# Sheet1.net
KiCad netlist of a schematic drawn in Altium Designer
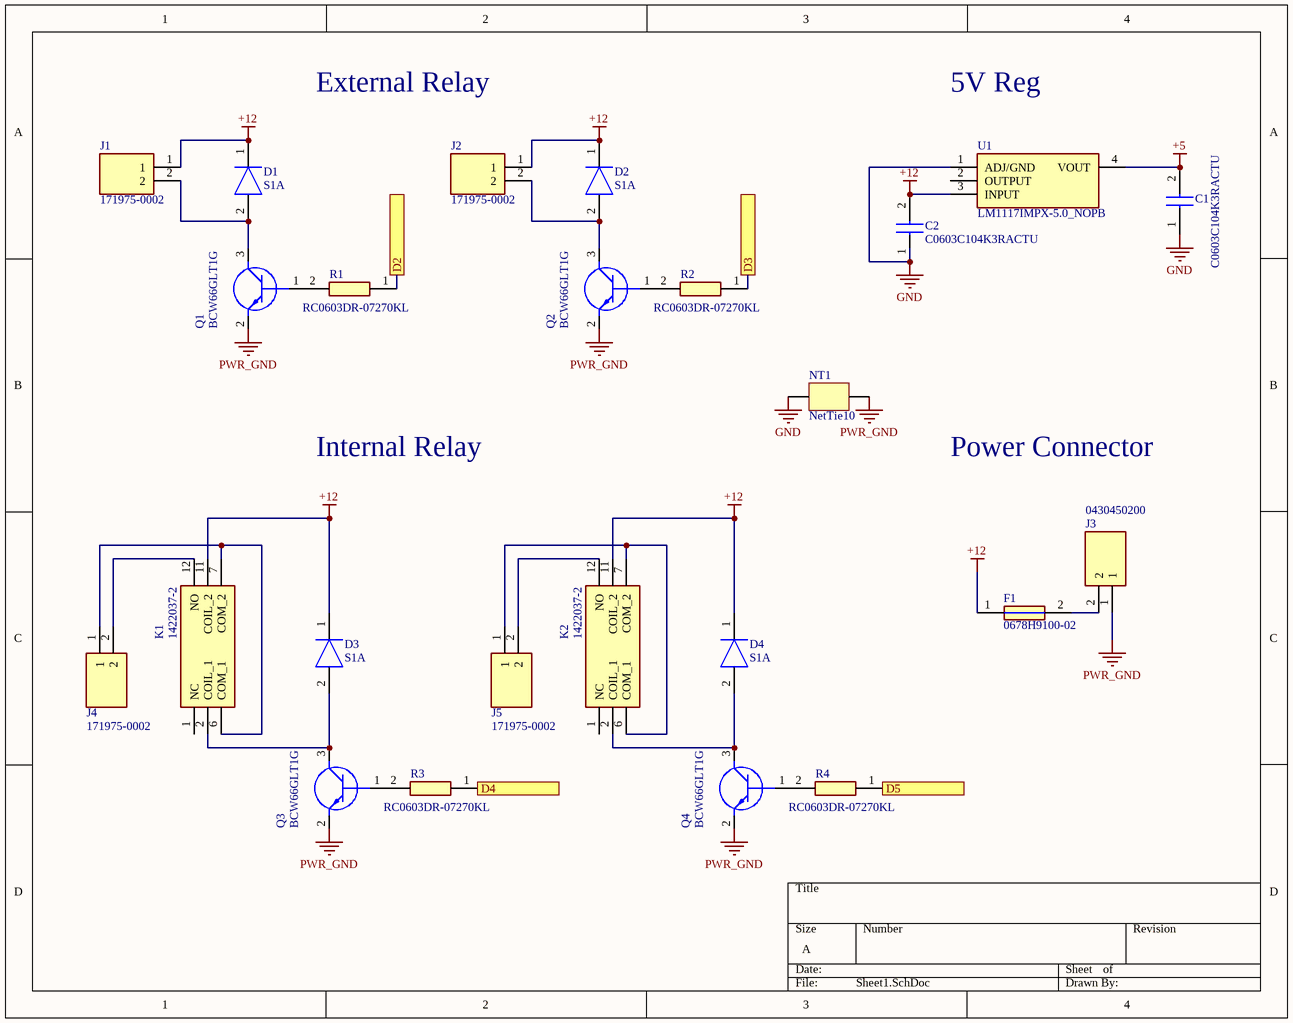
[diagram p0: Sheet1.SchDoc]

(export (version "E")
  (design (tool "Eeschema 10.0.6"))
  (components
    (comp (ref "C1")
      (value "C0603C104K3RACTU")
      (footprint "SamacSys:CAPC1608X95N")
      (description "Capacitor")
      (fields (field (name "MOUSER PART NUMBER") "80-C0603C104K3R"))
      (libsource (lib "*") (part "C0603C104K3RACTU"))
    )
    (comp (ref "C2")
      (value "C0603C104K3RACTU")
      (footprint "SamacSys:CAPC1608X95N")
      (description "Capacitor")
      (fields (field (name "MOUSER PART NUMBER") "80-C0603C104K3R"))
      (libsource (lib "*") (part "C0603C104K3RACTU"))
    )
    (comp (ref "D1")
      (value "S1A")
      (footprint "SamacSys:DIOM5227X270N")
      (description "Diode")
      (fields (field (name "MOUSER PART NUMBER") "512-S1A"))
      (libsource (lib "*") (part "S1A"))
    )
    (comp (ref "D2")
      (value "S1A")
      (footprint "SamacSys:DIOM5227X270N")
      (description "Diode")
      (fields (field (name "MOUSER PART NUMBER") "512-S1A"))
      (libsource (lib "*") (part "S1A"))
    )
    (comp (ref "D3")
      (value "S1A")
      (footprint "SamacSys:DIOM5227X270N")
      (description "Diode")
      (fields (field (name "MOUSER PART NUMBER") "512-S1A"))
      (libsource (lib "*") (part "S1A"))
    )
    (comp (ref "D4")
      (value "S1A")
      (footprint "SamacSys:DIOM5227X270N")
      (description "Diode")
      (fields (field (name "MOUSER PART NUMBER") "512-S1A"))
      (libsource (lib "*") (part "S1A"))
    )
    (comp (ref "F1")
      (value "0678H9100-02")
      (footprint "SamacSys:FUSC9830X318N")
      (description "Fuse")
      (fields (field (name "MOUSER PART NUMBER") "530-0678H9100-02"))
      (libsource (lib "*") (part "0678H9100-02"))
    )
    (comp (ref "J1")
      (value "171975-0002")
      (footprint "SamacSys:1719750002")
      (description "Connector")
      (fields (field (name "MOUSER PART NUMBER") "538-171975-0002"))
      (libsource (lib "*") (part "171975-0002"))
    )
    (comp (ref "J2")
      (value "171975-0002")
      (footprint "SamacSys:1719750002")
      (description "Connector")
      (fields (field (name "MOUSER PART NUMBER") "538-171975-0002"))
      (libsource (lib "*") (part "171975-0002"))
    )
    (comp (ref "J3")
      (value "0430450200")
      (footprint "SamacSys:43045-0200")
      (description "Connector")
      (libsource (lib "*") (part "0430450200"))
    )
    (comp (ref "J4")
      (value "171975-0002")
      (footprint "SamacSys:1719750002")
      (description "Connector")
      (fields (field (name "MOUSER PART NUMBER") "538-171975-0002"))
      (libsource (lib "") (part "171975-0002_1"))
    )
    (comp (ref "J5")
      (value "171975-0002")
      (footprint "SamacSys:1719750002")
      (description "Connector")
      (fields (field (name "MOUSER PART NUMBER") "538-171975-0002"))
      (libsource (lib "") (part "171975-0002_1"))
    )
    (comp (ref "K1")
      (value "1422037-2")
      (footprint "SamacSys:14220372")
      (description "Relay or Contactor")
      (fields (field (name "MOUSER PART NUMBER") "655-1422037-2"))
      (libsource (lib "PCB_Project") (part "1422037-2"))
    )
    (comp (ref "K2")
      (value "1422037-2")
      (footprint "SamacSys:14220372")
      (description "Relay or Contactor")
      (fields (field (name "MOUSER PART NUMBER") "655-1422037-2"))
      (libsource (lib "PCB_Project") (part "1422037-2"))
    )
    (comp (ref "NT1")
      (value "NetTie10")
      (footprint "NetTie")
      (libsource (lib "PCB_Project") (part "NetTie10"))
    )
    (comp (ref "Q1")
      (value "BCW66GLT1G")
      (footprint "SamacSys:SOT95P237X111-3N")
      (description "Transistor BJT NPN")
      (fields (field (name "MOUSER PART NUMBER") "863-BCW66GLT1G"))
      (libsource (lib "*") (part "BCW66GLT1G"))
    )
    (comp (ref "Q2")
      (value "BCW66GLT1G")
      (footprint "SamacSys:SOT95P237X111-3N")
      (description "Transistor BJT NPN")
      (fields (field (name "MOUSER PART NUMBER") "863-BCW66GLT1G"))
      (libsource (lib "*") (part "BCW66GLT1G"))
    )
    (comp (ref "Q3")
      (value "BCW66GLT1G")
      (footprint "SamacSys:SOT95P237X111-3N")
      (description "Transistor BJT NPN")
      (fields (field (name "MOUSER PART NUMBER") "863-BCW66GLT1G"))
      (libsource (lib "*") (part "BCW66GLT1G"))
    )
    (comp (ref "Q4")
      (value "BCW66GLT1G")
      (footprint "SamacSys:SOT95P237X111-3N")
      (description "Transistor BJT NPN")
      (fields (field (name "MOUSER PART NUMBER") "863-BCW66GLT1G"))
      (libsource (lib "*") (part "BCW66GLT1G"))
    )
    (comp (ref "R1")
      (value "RC0603DR-07270KL")
      (footprint "SamacSys:RESC1608X55N")
      (description "Resistor")
      (libsource (lib "*") (part "RC0603DR-07270KL"))
    )
    (comp (ref "R2")
      (value "RC0603DR-07270KL")
      (footprint "SamacSys:RESC1608X55N")
      (description "Resistor")
      (libsource (lib "*") (part "RC0603DR-07270KL"))
    )
    (comp (ref "R3")
      (value "RC0603DR-07270KL")
      (footprint "SamacSys:RESC1608X55N")
      (description "Resistor")
      (libsource (lib "*") (part "RC0603DR-07270KL"))
    )
    (comp (ref "R4")
      (value "RC0603DR-07270KL")
      (footprint "SamacSys:RESC1608X55N")
      (description "Resistor")
      (libsource (lib "*") (part "RC0603DR-07270KL"))
    )
    (comp (ref "U1")
      (value "LM1117IMPX-5.0_NOPB")
      (footprint "SamacSys:SOT230P700X180-4N")
      (description "Undefined or Miscellaneous")
      (fields
        (field (name "MANUFACTURER_PART_NUMBER") "LM1117IMPX-5.0/NOPB")
        (field (name "MOUSER PART NUMBER") "926-LM1117IMPX50NOPB")
      )
      (libsource (lib "*") (part "LM1117IMPX-5.0_NOPB"))
    )
  )
  (nets
    (net (code "1") (name "+5") (class "Default")
      (node (ref "C1") (pin "2") (pinfunction "2_2") (pintype "passive"))
      (node (ref "U1") (pin "4") (pinfunction "VOUT_4") (pintype "passive"))
    )
    (net (code "2") (name "+12") (class "Default")
      (node (ref "C2") (pin "2") (pinfunction "2_2") (pintype "passive"))
      (node (ref "D1") (pin "1") (pinfunction "K_1") (pintype "passive"))
      (node (ref "D2") (pin "1") (pinfunction "K_1") (pintype "passive"))
      (node (ref "D3") (pin "1") (pinfunction "K_1") (pintype "passive"))
      (node (ref "D4") (pin "1") (pinfunction "K_1") (pintype "passive"))
      (node (ref "F1") (pin "1") (pinfunction "1_1") (pintype "passive"))
      (node (ref "J1") (pin "1") (pinfunction "1_1") (pintype "passive"))
      (node (ref "J2") (pin "1") (pinfunction "1_1") (pintype "passive"))
      (node (ref "K1") (pin "11") (pinfunction "COIL_2_11") (pintype "passive"))
      (node (ref "K2") (pin "11") (pinfunction "COIL_2_11") (pintype "passive"))
      (node (ref "U1") (pin "3") (pinfunction "INPUT_3") (pintype "passive"))
    )
    (net (code "3") (name "/D2") (class "Default")
      (node (ref "R1") (pin "1") (pinfunction "1_1") (pintype "passive"))
    )
    (net (code "4") (name "/D3") (class "Default")
      (node (ref "R2") (pin "1") (pinfunction "1_1") (pintype "passive"))
    )
    (net (code "5") (name "/D4") (class "Default")
      (node (ref "R3") (pin "1") (pinfunction "1_1") (pintype "passive"))
    )
    (net (code "6") (name "/D5") (class "Default")
      (node (ref "R4") (pin "1") (pinfunction "1_1") (pintype "passive"))
    )
    (net (code "7") (name "GND") (class "Default")
      (node (ref "C1") (pin "1") (pinfunction "1_1") (pintype "passive"))
      (node (ref "C2") (pin "1") (pinfunction "1_1") (pintype "passive"))
      (node (ref "NT1") (pin "1") (pinfunction "1_1") (pintype "passive"))
      (node (ref "U1") (pin "1") (pinfunction "ADJ/GND_1") (pintype "passive"))
    )
    (net (code "8") (name "Net-(D1-A)") (class "Default")
      (node (ref "D1") (pin "2") (pinfunction "A_2") (pintype "passive"))
      (node (ref "J1") (pin "2") (pinfunction "2_2") (pintype "passive"))
      (node (ref "Q1") (pin "3") (pinfunction "C_3") (pintype "passive"))
    )
    (net (code "9") (name "Net-(D2-A)") (class "Default")
      (node (ref "D2") (pin "2") (pinfunction "A_2") (pintype "passive"))
      (node (ref "J2") (pin "2") (pinfunction "2_2") (pintype "passive"))
      (node (ref "Q2") (pin "3") (pinfunction "C_3") (pintype "passive"))
    )
    (net (code "10") (name "Net-(D3-A)") (class "Default")
      (node (ref "D3") (pin "2") (pinfunction "A_2") (pintype "passive"))
      (node (ref "K1") (pin "2") (pinfunction "COIL_1_2") (pintype "passive"))
      (node (ref "Q3") (pin "3") (pinfunction "C_3") (pintype "passive"))
    )
    (net (code "11") (name "Net-(D4-A)") (class "Default")
      (node (ref "D4") (pin "2") (pinfunction "A_2") (pintype "passive"))
      (node (ref "K2") (pin "2") (pinfunction "COIL_1_2") (pintype "passive"))
      (node (ref "Q4") (pin "3") (pinfunction "C_3") (pintype "passive"))
    )
    (net (code "12") (name "Net-(F1-Pad2)") (class "Default")
      (node (ref "F1") (pin "2") (pinfunction "2_2") (pintype "passive"))
      (node (ref "J3") (pin "2") (pinfunction "2_2") (pintype "passive"))
    )
    (net (code "13") (name "Net-(K1-COM_1)") (class "Default")
      (node (ref "J4") (pin "1") (pinfunction "1_1") (pintype "passive"))
      (node (ref "K1") (pin "6") (pinfunction "COM_1_6") (pintype "passive"))
      (node (ref "K1") (pin "7") (pinfunction "COM_2_7") (pintype "passive"))
    )
    (net (code "14") (name "Net-(K1-NO)") (class "Default")
      (node (ref "J4") (pin "2") (pinfunction "2_2") (pintype "passive"))
      (node (ref "K1") (pin "12") (pinfunction "NO_12") (pintype "passive"))
    )
    (net (code "15") (name "Net-(K2-COM_1)") (class "Default")
      (node (ref "J5") (pin "1") (pinfunction "1_1") (pintype "passive"))
      (node (ref "K2") (pin "6") (pinfunction "COM_1_6") (pintype "passive"))
      (node (ref "K2") (pin "7") (pinfunction "COM_2_7") (pintype "passive"))
    )
    (net (code "16") (name "Net-(K2-NO)") (class "Default")
      (node (ref "J5") (pin "2") (pinfunction "2_2") (pintype "passive"))
      (node (ref "K2") (pin "12") (pinfunction "NO_12") (pintype "passive"))
    )
    (net (code "17") (name "Net-(Q1-B)") (class "Default")
      (node (ref "Q1") (pin "1") (pinfunction "B_1") (pintype "passive"))
      (node (ref "R1") (pin "2") (pinfunction "2_2") (pintype "passive"))
    )
    (net (code "18") (name "Net-(Q2-B)") (class "Default")
      (node (ref "Q2") (pin "1") (pinfunction "B_1") (pintype "passive"))
      (node (ref "R2") (pin "2") (pinfunction "2_2") (pintype "passive"))
    )
    (net (code "19") (name "Net-(Q3-B)") (class "Default")
      (node (ref "Q3") (pin "1") (pinfunction "B_1") (pintype "passive"))
      (node (ref "R3") (pin "2") (pinfunction "2_2") (pintype "passive"))
    )
    (net (code "20") (name "Net-(Q4-B)") (class "Default")
      (node (ref "Q4") (pin "1") (pinfunction "B_1") (pintype "passive"))
      (node (ref "R4") (pin "2") (pinfunction "2_2") (pintype "passive"))
    )
    (net (code "21") (name "PWR_GND") (class "Default")
      (node (ref "J3") (pin "1") (pinfunction "1_1") (pintype "passive"))
      (node (ref "NT1") (pin "2") (pinfunction "2_2") (pintype "passive"))
      (node (ref "Q1") (pin "2") (pinfunction "E_2") (pintype "passive"))
      (node (ref "Q2") (pin "2") (pinfunction "E_2") (pintype "passive"))
      (node (ref "Q3") (pin "2") (pinfunction "E_2") (pintype "passive"))
      (node (ref "Q4") (pin "2") (pinfunction "E_2") (pintype "passive"))
    )
    (net (code "22") (name "unconnected-(K1-NC-Pad1)") (class "Default")
      (node (ref "K1") (pin "1") (pinfunction "NC_1") (pintype "passive"))
    )
    (net (code "23") (name "unconnected-(K2-NC-Pad1)") (class "Default")
      (node (ref "K2") (pin "1") (pinfunction "NC_1") (pintype "passive"))
    )
    (net (code "24") (name "unconnected-(U1-OUTPUT-Pad2)") (class "Default")
      (node (ref "U1") (pin "2") (pinfunction "OUTPUT_2") (pintype "passive"))
    )
  )
)
